# MP2359-3_3v.net
KiCad netlist of a schematic drawn in Altium Designer
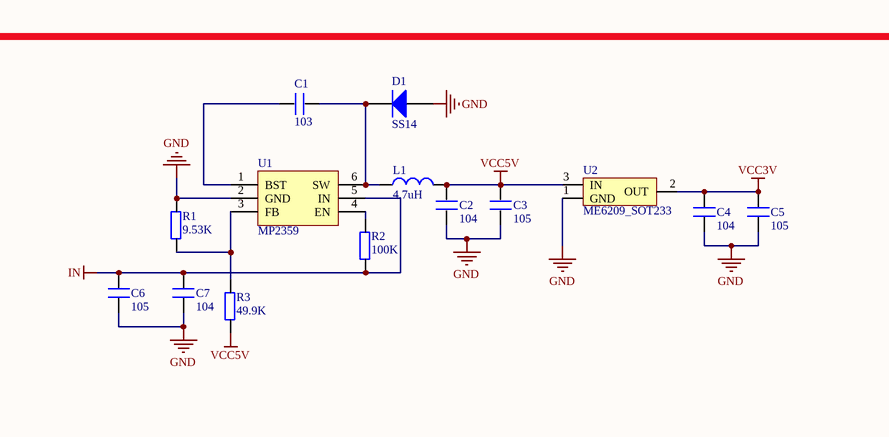
[diagram p0: MP2359-3.3v.SchDoc, left]

(export (version "E")
  (design (tool "Eeschema 10.0.6"))
  (components
    (comp (ref "C1") (value "103") (footprint "C_0805") (libsource (lib "Mylib") (part "C")))
    (comp (ref "C2") (value "104") (footprint "C_0805") (libsource (lib "Mylib") (part "C")))
    (comp (ref "C3") (value "105") (footprint "C_0805") (libsource (lib "Mylib") (part "C")))
    (comp (ref "C4") (value "104") (footprint "C_0805") (libsource (lib "Mylib") (part "C")))
    (comp (ref "C5") (value "105") (footprint "C_0805") (libsource (lib "Mylib") (part "C")))
    (comp (ref "C6") (value "105") (footprint "C_0805") (libsource (lib "Mylib") (part "C")))
    (comp (ref "C7") (value "104") (footprint "C_0805") (libsource (lib "Mylib") (part "C")))
    (comp (ref "D1")
      (value "Diode")
      (footprint "DIODE-SMA")
      (description "二极管")
      (fields (field (name "TYPE") "SS14") (field (name "PUBLISHER") "Altium Limited"))
      (libsource (lib "Mylib") (part "Diode"))
    )
    (comp (ref "L1")
      (value "4.7uH")
      (footprint "L-SMD-7")
      (description "电感")
      (fields (field (name "Comment") "Inductor") (field (name "PUBLISHER") "Altium Limited"))
      (libsource (lib "Mylib") (part "Inductor"))
    )
    (comp (ref "R1") (value "9.53K") (footprint "R0805") (libsource (lib "Mylib") (part "R")))
    (comp (ref "R2") (value "100K") (footprint "R0805") (libsource (lib "Mylib") (part "R")))
    (comp (ref "R3") (value "49.9K") (footprint "R0805") (libsource (lib "Mylib") (part "R")))
    (comp (ref "U1") (value "MP2359") (footprint "SOT23-6") (libsource (lib "Mylib") (part "MP2359")))
    (comp (ref "U2")
      (value "ME6209_SOT233")
      (footprint "SOT-23 - duplicate1")
      (libsource (lib "Mylib") (part "ME6209"))
    )
  )
  (nets
    (net (code "1") (name "GND") (class "Default")
      (node (ref "C2") (pin "1") (pintype "passive"))
      (node (ref "C3") (pin "1") (pintype "passive"))
      (node (ref "C4") (pin "1") (pintype "passive"))
      (node (ref "C5") (pin "1") (pintype "passive"))
      (node (ref "C6") (pin "1") (pintype "passive"))
      (node (ref "C7") (pin "1") (pintype "passive"))
      (node (ref "D1") (pin "1") (pinfunction "A_1") (pintype "passive"))
      (node (ref "R1") (pin "1") (pintype "passive"))
      (node (ref "U1") (pin "2") (pinfunction "GND_2") (pintype "power_in"))
      (node (ref "U2") (pin "1") (pinfunction "GND_1") (pintype "passive"))
    )
    (net (code "2") (name "IN") (class "Default")
      (node (ref "C6") (pin "2") (pintype "passive"))
      (node (ref "C7") (pin "2") (pintype "passive"))
      (node (ref "R2") (pin "2") (pintype "passive"))
      (node (ref "U1") (pin "5") (pinfunction "IN_5") (pintype "passive"))
    )
    (net (code "3") (name "Net-(D1-K)") (class "Default")
      (node (ref "C1") (pin "2") (pintype "passive"))
      (node (ref "D1") (pin "2") (pinfunction "K_2") (pintype "passive"))
      (node (ref "L1") (pin "1") (pinfunction "1_1") (pintype "passive"))
      (node (ref "U1") (pin "6") (pinfunction "SW_6") (pintype "passive"))
    )
    (net (code "4") (name "Net-(U1-BST)") (class "Default")
      (node (ref "C1") (pin "1") (pintype "passive"))
      (node (ref "U1") (pin "1") (pinfunction "BST_1") (pintype "passive"))
    )
    (net (code "5") (name "Net-(U1-EN)") (class "Default")
      (node (ref "R2") (pin "1") (pintype "passive"))
      (node (ref "U1") (pin "4") (pinfunction "EN_4") (pintype "passive"))
    )
    (net (code "6") (name "Net-(U1-FB)") (class "Default")
      (node (ref "R1") (pin "2") (pintype "passive"))
      (node (ref "R3") (pin "1") (pintype "passive"))
      (node (ref "U1") (pin "3") (pinfunction "FB_3") (pintype "passive"))
    )
    (net (code "7") (name "VCC3V") (class "Default")
      (node (ref "C4") (pin "2") (pintype "passive"))
      (node (ref "C5") (pin "2") (pintype "passive"))
      (node (ref "U2") (pin "2") (pinfunction "OUT_2") (pintype "passive"))
    )
    (net (code "8") (name "VCC5V") (class "Default")
      (node (ref "C2") (pin "2") (pintype "passive"))
      (node (ref "C3") (pin "2") (pintype "passive"))
      (node (ref "L1") (pin "2") (pinfunction "2_2") (pintype "passive"))
      (node (ref "R3") (pin "2") (pintype "passive"))
      (node (ref "U2") (pin "3") (pinfunction "IN_3") (pintype "passive"))
    )
  )
)
